# DM0250_BW235_OV_9282.net
KiCad netlist of a schematic drawn in Altium Designer
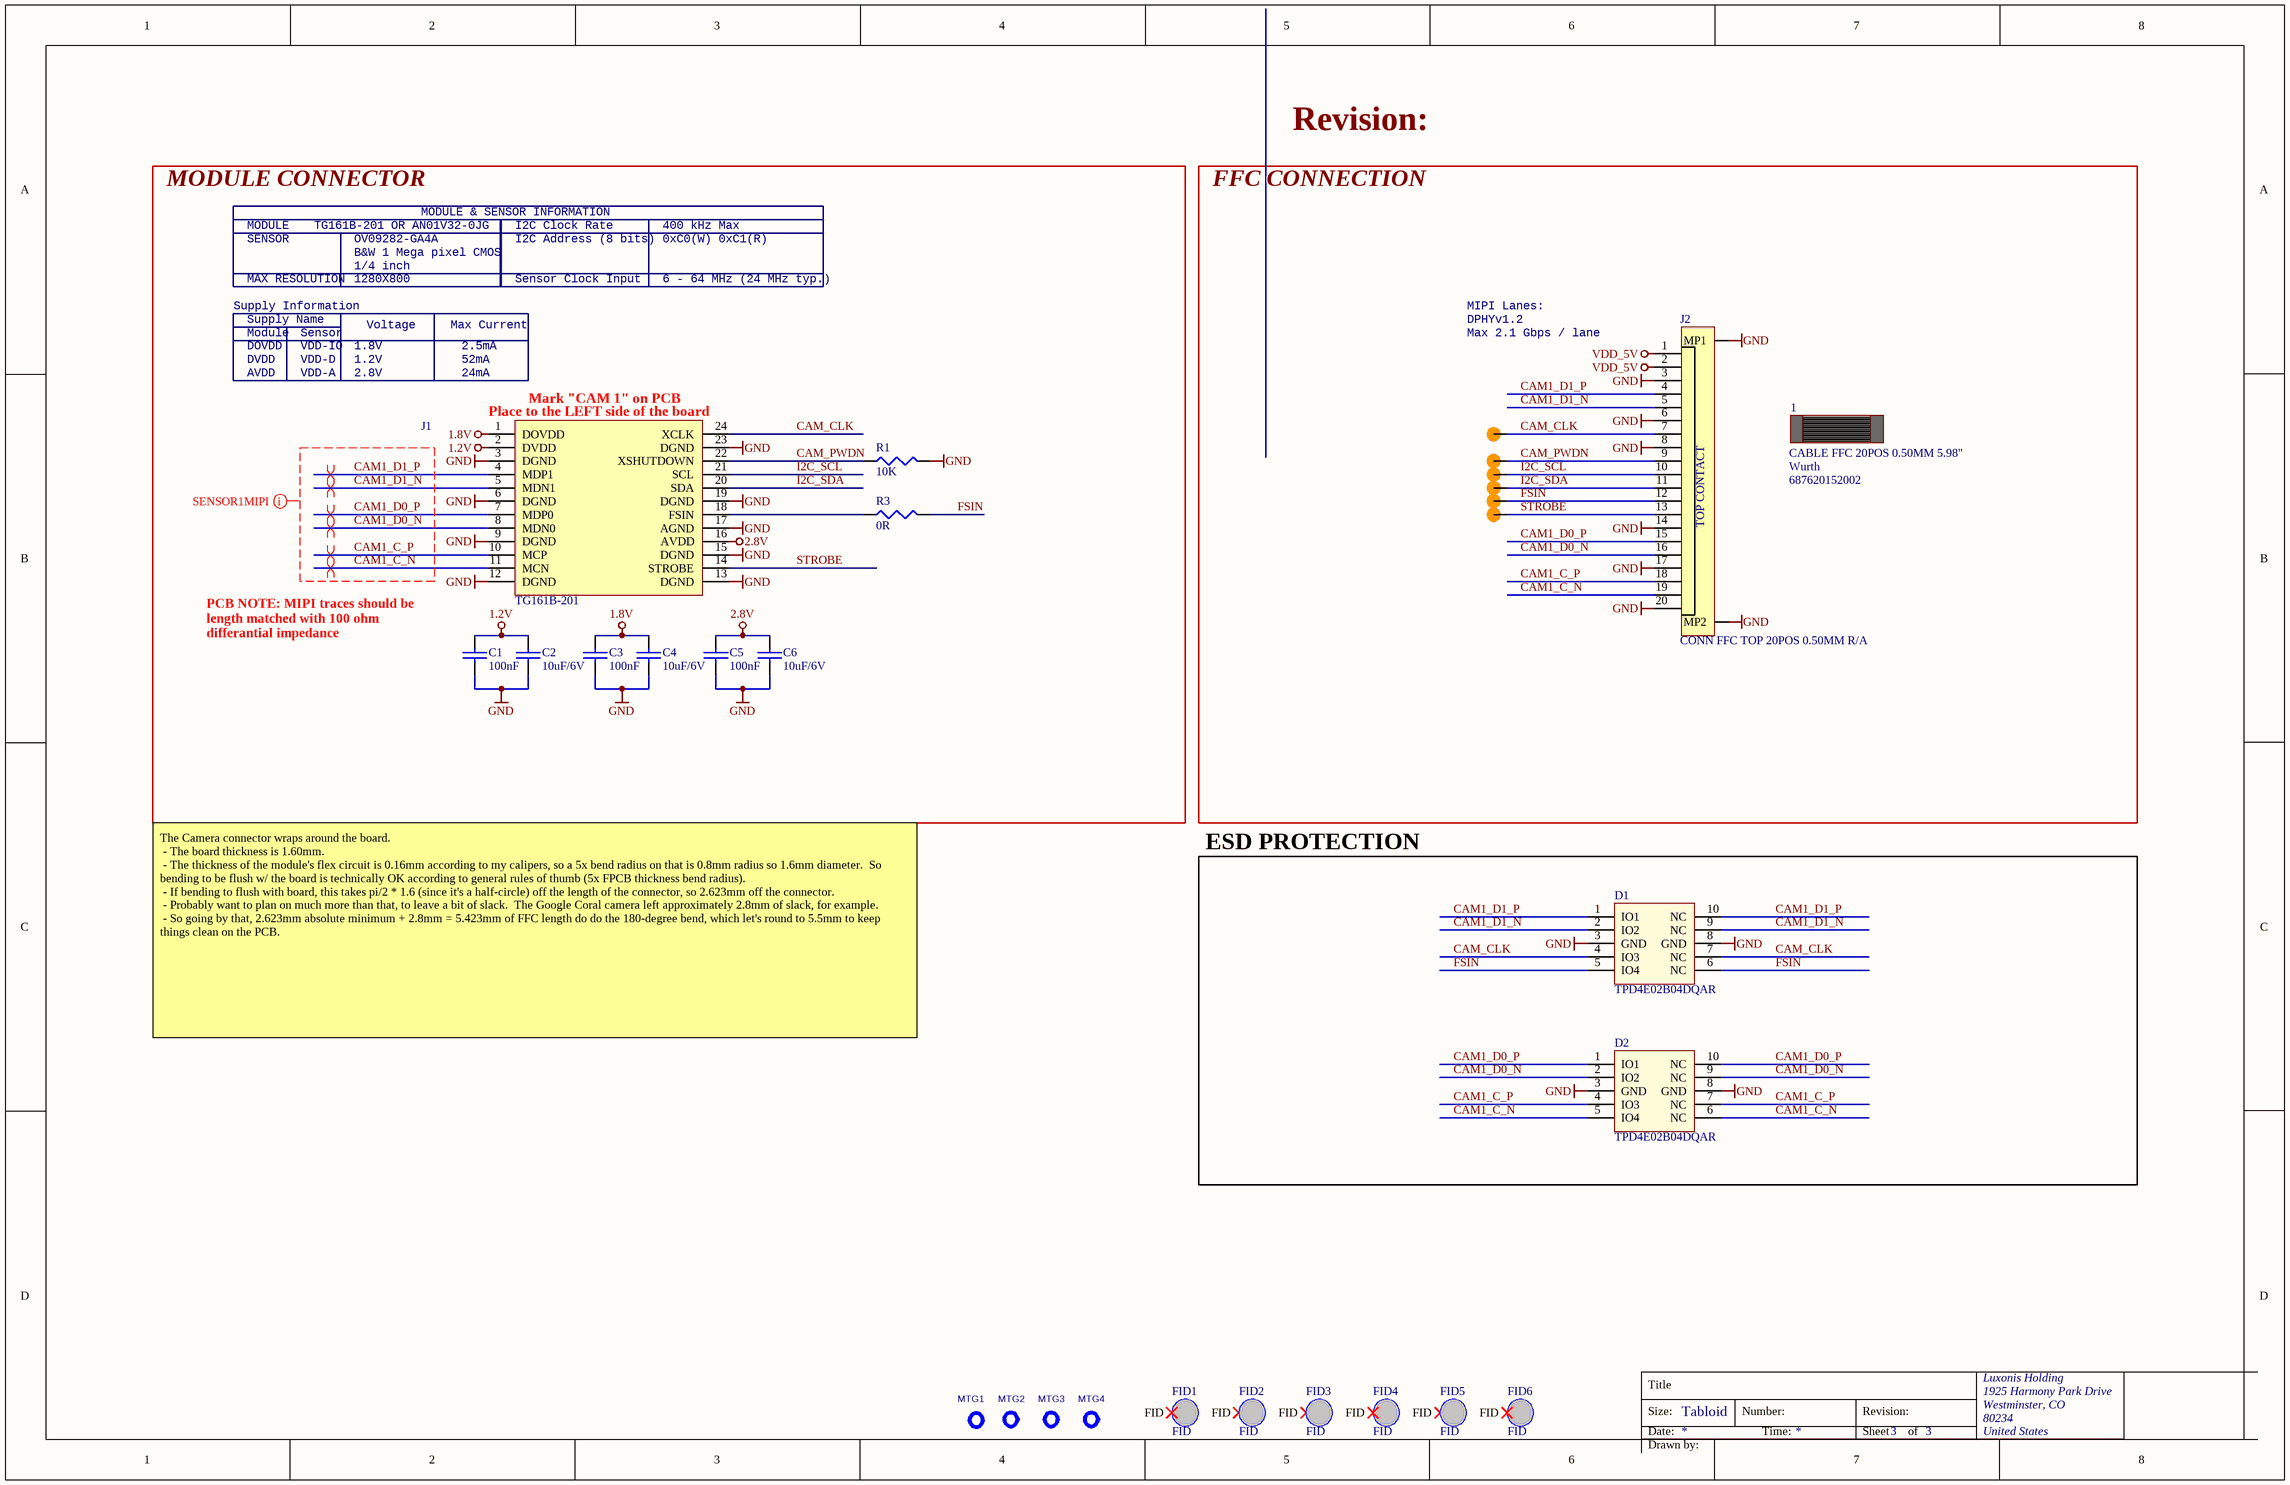
[diagram p0: DM0250_BW235_OV_9282.SchDoc]

(export (version "E")
  (design (tool "Eeschema 10.0.6"))
  (components
    (comp (ref "1")
      (value "687620152002")
      (description "20 pin FFC cable 15cm")
      (fields (field (name "ICCO PN") "CABLE FFC 20POS 0.50MM 5.98\"") (field (name "MAN") "Wurth"))
      (libsource (lib "RS-CONN") (part "26 pin FFC cable 15cm"))
    )
    (comp (ref "C1")
      (value "100nF")
      (footprint "0402")
      (description "SMD Multilayer Ceramic Capacitor, 0402 [1005 Metric], 0.1 µF, 10 V, ± 10%, X5R")
      (libsource (lib "MV0250_R0M0E0") (part "CAP"))
    )
    (comp (ref "C2")
      (value "10uF/6V")
      (footprint "0603")
      (description "CC0603MRX5R5BB106  SMD Multilayer Ceramic Capacitor, 0603 [1608 Metric], 10 µF, 6.3 V, ± 20%, X5R")
      (libsource (lib "MV0250_R0M0E0") (part "CAP"))
    )
    (comp (ref "C3")
      (value "100nF")
      (footprint "0402")
      (description "SMD Multilayer Ceramic Capacitor, 0402 [1005 Metric], 0.1 µF, 10 V, ± 10%, X5R")
      (libsource (lib "MV0250_R0M0E0") (part "CAP"))
    )
    (comp (ref "C4")
      (value "10uF/6V")
      (footprint "0603")
      (description "CC0603MRX5R5BB106  SMD Multilayer Ceramic Capacitor, 0603 [1608 Metric], 10 µF, 6.3 V, ± 20%, X5R")
      (libsource (lib "MV0250_R0M0E0") (part "CAP"))
    )
    (comp (ref "C5")
      (value "100nF")
      (footprint "0402")
      (description "SMD Multilayer Ceramic Capacitor, 0402 [1005 Metric], 0.1 µF, 10 V, ± 10%, X5R")
      (libsource (lib "MV0250_R0M0E0") (part "CAP"))
    )
    (comp (ref "C6")
      (value "10uF/6V")
      (footprint "0603")
      (description "CC0603MRX5R5BB106  SMD Multilayer Ceramic Capacitor, 0603 [1608 Metric], 10 µF, 6.3 V, ± 20%, X5R")
      (libsource (lib "MV0250_R0M0E0") (part "CAP"))
    )
    (comp (ref "D1")
      (value "TPD4E02B04DQAR")
      (footprint "LuxonisMaster:TPD4E02B04DQAR")
      (libsource (lib "LuxonisMaster") (part "TPD4E02B04DQAR"))
    )
    (comp (ref "D2")
      (value "TPD4E02B04DQAR")
      (footprint "LuxonisMaster:TPD4E02B04DQAR")
      (libsource (lib "LuxonisMaster") (part "TPD4E02B04DQAR"))
    )
    (comp (ref "FID1")
      (value "FID")
      (footprint "Luxonis:FIDUCIAL_1MM")
      (description "Fiducial mark")
      (libsource (lib "MV0250_R0M0E0") (part "FID"))
    )
    (comp (ref "FID2")
      (value "FID")
      (footprint "Luxonis:FIDUCIAL_1MM")
      (description "Fiducial mark")
      (libsource (lib "MV0250_R0M0E0") (part "FID"))
    )
    (comp (ref "FID3")
      (value "FID")
      (footprint "Luxonis:FIDUCIAL_1MM")
      (description "Fiducial mark")
      (libsource (lib "MV0250_R0M0E0") (part "FID"))
    )
    (comp (ref "FID4")
      (value "FID")
      (footprint "Luxonis:FIDUCIAL_1MM")
      (description "Fiducial mark")
      (libsource (lib "MV0250_R0M0E0") (part "FID"))
    )
    (comp (ref "FID5")
      (value "FID")
      (footprint "Luxonis:FIDUCIAL_1MM")
      (description "Fiducial mark")
      (libsource (lib "MV0250_R0M0E0") (part "FID"))
    )
    (comp (ref "FID6")
      (value "FID")
      (footprint "Luxonis:FIDUCIAL_1MM")
      (description "Fiducial mark")
      (libsource (lib "MV0250_R0M0E0") (part "FID"))
    )
    (comp (ref "J1")
      (value "TG161B-201")
      (footprint "TG161B-201 / AN01V32 - Board Wrap")
      (description "24 way, 2row baord to board connector SMD")
      (libsource (lib "BG0250") (part "TG161B-201"))
    )
    (comp (ref "J2")
      (value "CONN FFC TOP 20POS 0.50MM R/A")
      (footprint "5052782033")
      (description "0.5 Ffc Zif Btm Cont Embt Pkg 0.5 Fpc Zif Btm FS19")
      (libsource (lib "DM1098FFC") (part "5052782033"))
    )
    (comp (ref "MTG1")
      (value "MTG-HOLE")
      (footprint "Luxonis:Hole_2.2mm")
      (description "Mounting Hole")
      (libsource (lib "Luxonis") (part "MTG-HOLE-NO-PLATE"))
    )
    (comp (ref "MTG2")
      (value "MTG-HOLE")
      (footprint "Luxonis:Hole_2.2mm")
      (description "Mounting Hole")
      (libsource (lib "Luxonis") (part "MTG-HOLE-NO-PLATE"))
    )
    (comp (ref "MTG3")
      (value "MTG-HOLE")
      (footprint "Luxonis:Hole_2.2mm")
      (description "Mounting Hole")
      (libsource (lib "Luxonis") (part "MTG-HOLE-NO-PLATE"))
    )
    (comp (ref "MTG4")
      (value "MTG-HOLE")
      (footprint "Luxonis:Hole_2.2mm")
      (description "Mounting Hole")
      (libsource (lib "Luxonis") (part "MTG-HOLE-NO-PLATE"))
    )
    (comp (ref "R1")
      (value "10K")
      (footprint "0603")
      (description "SMD Chip Resistor, 10 kohm, 75 V, 0603 [1608 Metric], 100 mW, ± 1%")
      (libsource (lib "MV0250_R0M0E0") (part "RES1"))
    )
    (comp (ref "R3")
      (value "0R")
      (footprint "0603")
      (description "SMD Chip Resistor, Thick Film, 0 ohm, 75 V, 0603 [1608 Metric], 100 mW")
      (libsource (lib "MV0250_R0M0E0") (part "RES1"))
    )
    (comp (ref "TP1")
      (value "TP_SMD")
      (footprint "TP_0.75MM_SMD_NO-SILK")
      (description "circular pad test point, SMD")
      (libsource (lib "Luxonis") (part "TP_SMD"))
    )
    (comp (ref "TP2")
      (value "TP_SMD")
      (footprint "TP_0.75MM_SMD_NO-SILK")
      (description "circular pad test point, SMD")
      (libsource (lib "Luxonis") (part "TP_SMD"))
    )
    (comp (ref "TP3")
      (value "TP_SMD")
      (footprint "TP_0.75MM_SMD_NO-SILK")
      (description "circular pad test point, SMD")
      (libsource (lib "Luxonis") (part "TP_SMD"))
    )
    (comp (ref "TP4")
      (value "TP_SMD")
      (footprint "TP_0.75MM_SMD_NO-SILK")
      (description "circular pad test point, SMD")
      (libsource (lib "Luxonis") (part "TP_SMD"))
    )
    (comp (ref "TP5")
      (value "TP_SMD")
      (footprint "TP_0.75MM_SMD_NO-SILK")
      (description "circular pad test point, SMD")
      (libsource (lib "Luxonis") (part "TP_SMD"))
    )
    (comp (ref "TP6")
      (value "TP_SMD")
      (footprint "TP_0.75MM_SMD_NO-SILK")
      (description "circular pad test point, SMD")
      (libsource (lib "Luxonis") (part "TP_SMD"))
    )
  )
  (nets
    (net (code "1") (name "/CAM1_C_N") (class "Default")
      (node (ref "D2") (pin "5") (pinfunction "IO4_5") (pintype "passive"))
      (node (ref "D2") (pin "6") (pinfunction "NC_6") (pintype "passive"))
      (node (ref "J1") (pin "11") (pinfunction "MCN_11") (pintype "passive"))
      (node (ref "J2") (pin "19") (pinfunction "19_19") (pintype "passive"))
    )
    (net (code "2") (name "/CAM1_C_P") (class "Default")
      (node (ref "D2") (pin "4") (pinfunction "IO3_4") (pintype "passive"))
      (node (ref "D2") (pin "7") (pinfunction "NC_7") (pintype "passive"))
      (node (ref "J1") (pin "10") (pinfunction "MCP_10") (pintype "passive"))
      (node (ref "J2") (pin "18") (pinfunction "18_18") (pintype "passive"))
    )
    (net (code "3") (name "/CAM1_D0_N") (class "Default")
      (node (ref "D2") (pin "2") (pinfunction "IO2_2") (pintype "passive"))
      (node (ref "D2") (pin "9") (pinfunction "NC_9") (pintype "passive"))
      (node (ref "J1") (pin "8") (pinfunction "MDN0_8") (pintype "passive"))
      (node (ref "J2") (pin "16") (pinfunction "16_16") (pintype "passive"))
    )
    (net (code "4") (name "/CAM1_D0_P") (class "Default")
      (node (ref "D2") (pin "1") (pinfunction "IO1_1") (pintype "passive"))
      (node (ref "D2") (pin "10") (pinfunction "NC_10") (pintype "passive"))
      (node (ref "J1") (pin "7") (pinfunction "MDP0_7") (pintype "passive"))
      (node (ref "J2") (pin "15") (pinfunction "15_15") (pintype "passive"))
    )
    (net (code "5") (name "/CAM1_D1_N") (class "Default")
      (node (ref "D1") (pin "2") (pinfunction "IO2_2") (pintype "passive"))
      (node (ref "D1") (pin "9") (pinfunction "NC_9") (pintype "passive"))
      (node (ref "J1") (pin "5") (pinfunction "MDN1_5") (pintype "passive"))
      (node (ref "J2") (pin "5") (pinfunction "5_5") (pintype "passive"))
    )
    (net (code "6") (name "/CAM1_D1_P") (class "Default")
      (node (ref "D1") (pin "1") (pinfunction "IO1_1") (pintype "passive"))
      (node (ref "D1") (pin "10") (pinfunction "NC_10") (pintype "passive"))
      (node (ref "J1") (pin "4") (pinfunction "MDP1_4") (pintype "passive"))
      (node (ref "J2") (pin "4") (pinfunction "4_4") (pintype "passive"))
    )
    (net (code "7") (name "/CAM_CLK") (class "Default")
      (node (ref "D1") (pin "4") (pinfunction "IO3_4") (pintype "passive"))
      (node (ref "D1") (pin "7") (pinfunction "NC_7") (pintype "passive"))
      (node (ref "J1") (pin "24") (pinfunction "XCLK_24") (pintype "passive"))
      (node (ref "J2") (pin "7") (pinfunction "7_7") (pintype "passive"))
      (node (ref "TP1") (pin "1") (pintype "passive"))
    )
    (net (code "8") (name "/CAM_PWDN") (class "Default")
      (node (ref "J1") (pin "22") (pinfunction "XSHUTDOWN_22") (pintype "passive"))
      (node (ref "J2") (pin "9") (pinfunction "9_9") (pintype "passive"))
      (node (ref "R1") (pin "1") (pintype "passive"))
      (node (ref "TP2") (pin "1") (pintype "passive"))
    )
    (net (code "9") (name "/FSIN") (class "Default")
      (node (ref "D1") (pin "5") (pinfunction "IO4_5") (pintype "passive"))
      (node (ref "D1") (pin "6") (pinfunction "NC_6") (pintype "passive"))
      (node (ref "J2") (pin "12") (pinfunction "12_12") (pintype "passive"))
      (node (ref "R3") (pin "2") (pintype "passive"))
      (node (ref "TP5") (pin "1") (pintype "passive"))
    )
    (net (code "10") (name "/I2C_SCL") (class "Default")
      (node (ref "J1") (pin "21") (pinfunction "SCL_21") (pintype "passive"))
      (node (ref "J2") (pin "10") (pinfunction "10_10") (pintype "passive"))
      (node (ref "TP3") (pin "1") (pintype "passive"))
    )
    (net (code "11") (name "/I2C_SDA") (class "Default")
      (node (ref "J1") (pin "20") (pinfunction "SDA_20") (pintype "passive"))
      (node (ref "J2") (pin "11") (pinfunction "11_11") (pintype "passive"))
      (node (ref "TP4") (pin "1") (pintype "passive"))
    )
    (net (code "12") (name "/STROBE") (class "Default")
      (node (ref "J1") (pin "14") (pinfunction "STROBE_14") (pintype "passive"))
      (node (ref "J2") (pin "13") (pinfunction "13_13") (pintype "passive"))
      (node (ref "TP6") (pin "1") (pintype "passive"))
    )
    (net (code "13") (name "1.2V") (class "Default")
      (node (ref "C1") (pin "2") (pinfunction "2_2") (pintype "passive"))
      (node (ref "C2") (pin "2") (pinfunction "2_2") (pintype "passive"))
      (node (ref "J1") (pin "2") (pinfunction "DVDD_2") (pintype "passive"))
    )
    (net (code "14") (name "1.8V") (class "Default")
      (node (ref "C3") (pin "2") (pinfunction "2_2") (pintype "passive"))
      (node (ref "C4") (pin "2") (pinfunction "2_2") (pintype "passive"))
      (node (ref "J1") (pin "1") (pinfunction "DOVDD_1") (pintype "passive"))
    )
    (net (code "15") (name "2.8V") (class "Default")
      (node (ref "C5") (pin "2") (pinfunction "2_2") (pintype "passive"))
      (node (ref "C6") (pin "2") (pinfunction "2_2") (pintype "passive"))
      (node (ref "J1") (pin "16") (pinfunction "AVDD_16") (pintype "passive"))
    )
    (net (code "16") (name "GND") (class "Default")
      (node (ref "C1") (pin "1") (pinfunction "1_1") (pintype "passive"))
      (node (ref "C2") (pin "1") (pinfunction "1_1") (pintype "passive"))
      (node (ref "C3") (pin "1") (pinfunction "1_1") (pintype "passive"))
      (node (ref "C4") (pin "1") (pinfunction "1_1") (pintype "passive"))
      (node (ref "C5") (pin "1") (pinfunction "1_1") (pintype "passive"))
      (node (ref "C6") (pin "1") (pinfunction "1_1") (pintype "passive"))
      (node (ref "D1") (pin "3") (pinfunction "GND_3") (pintype "passive"))
      (node (ref "D1") (pin "8") (pinfunction "GND_8") (pintype "passive"))
      (node (ref "D2") (pin "3") (pinfunction "GND_3") (pintype "passive"))
      (node (ref "D2") (pin "8") (pinfunction "GND_8") (pintype "passive"))
      (node (ref "J1") (pin "12") (pinfunction "DGND_12") (pintype "passive"))
      (node (ref "J1") (pin "13") (pinfunction "DGND_13") (pintype "passive"))
      (node (ref "J1") (pin "15") (pinfunction "DGND_15") (pintype "passive"))
      (node (ref "J1") (pin "17") (pinfunction "AGND_17") (pintype "passive"))
      (node (ref "J1") (pin "19") (pinfunction "DGND_19") (pintype "passive"))
      (node (ref "J1") (pin "23") (pinfunction "DGND_23") (pintype "passive"))
      (node (ref "J1") (pin "3") (pinfunction "DGND_3") (pintype "passive"))
      (node (ref "J1") (pin "6") (pinfunction "DGND_6") (pintype "passive"))
      (node (ref "J1") (pin "9") (pinfunction "DGND_9") (pintype "passive"))
      (node (ref "J2") (pin "14") (pinfunction "14_14") (pintype "passive"))
      (node (ref "J2") (pin "17") (pinfunction "17_17") (pintype "passive"))
      (node (ref "J2") (pin "20") (pinfunction "20_20") (pintype "passive"))
      (node (ref "J2") (pin "3") (pinfunction "3_3") (pintype "passive"))
      (node (ref "J2") (pin "6") (pinfunction "6_6") (pintype "passive"))
      (node (ref "J2") (pin "8") (pinfunction "8_8") (pintype "passive"))
      (node (ref "J2") (pin "MP1") (pinfunction "MP1_MP1") (pintype "passive"))
      (node (ref "J2") (pin "MP2") (pinfunction "MP2_MP2") (pintype "passive"))
      (node (ref "R1") (pin "2") (pintype "passive"))
    )
    (net (code "17") (name "Net-(J1-FSIN)") (class "Default")
      (node (ref "J1") (pin "18") (pinfunction "FSIN_18") (pintype "passive"))
      (node (ref "R3") (pin "1") (pintype "passive"))
    )
    (net (code "18") (name "VDD_5V") (class "Default")
      (node (ref "J2") (pin "1") (pinfunction "1_1") (pintype "passive"))
      (node (ref "J2") (pin "2") (pinfunction "2_2") (pintype "passive"))
    )
    (net (code "19") (name "unconnected-(FID1-PadFID)") (class "Default")
      (node (ref "FID1") (pin "FID") (pinfunction "FID_FID") (pintype "input+no_connect"))
    )
    (net (code "20") (name "unconnected-(FID2-PadFID)") (class "Default")
      (node (ref "FID2") (pin "FID") (pinfunction "FID_FID") (pintype "input+no_connect"))
    )
    (net (code "21") (name "unconnected-(FID3-PadFID)") (class "Default")
      (node (ref "FID3") (pin "FID") (pinfunction "FID_FID") (pintype "input+no_connect"))
    )
    (net (code "22") (name "unconnected-(FID4-PadFID)") (class "Default")
      (node (ref "FID4") (pin "FID") (pinfunction "FID_FID") (pintype "input+no_connect"))
    )
    (net (code "23") (name "unconnected-(FID5-PadFID)") (class "Default")
      (node (ref "FID5") (pin "FID") (pinfunction "FID_FID") (pintype "input+no_connect"))
    )
    (net (code "24") (name "unconnected-(FID6-PadFID)") (class "Default")
      (node (ref "FID6") (pin "FID") (pinfunction "FID_FID") (pintype "input+no_connect"))
    )
  )
)
